# WSN_Atmega8a_V1_2.net
KiCad netlist of a schematic drawn in EAGLE
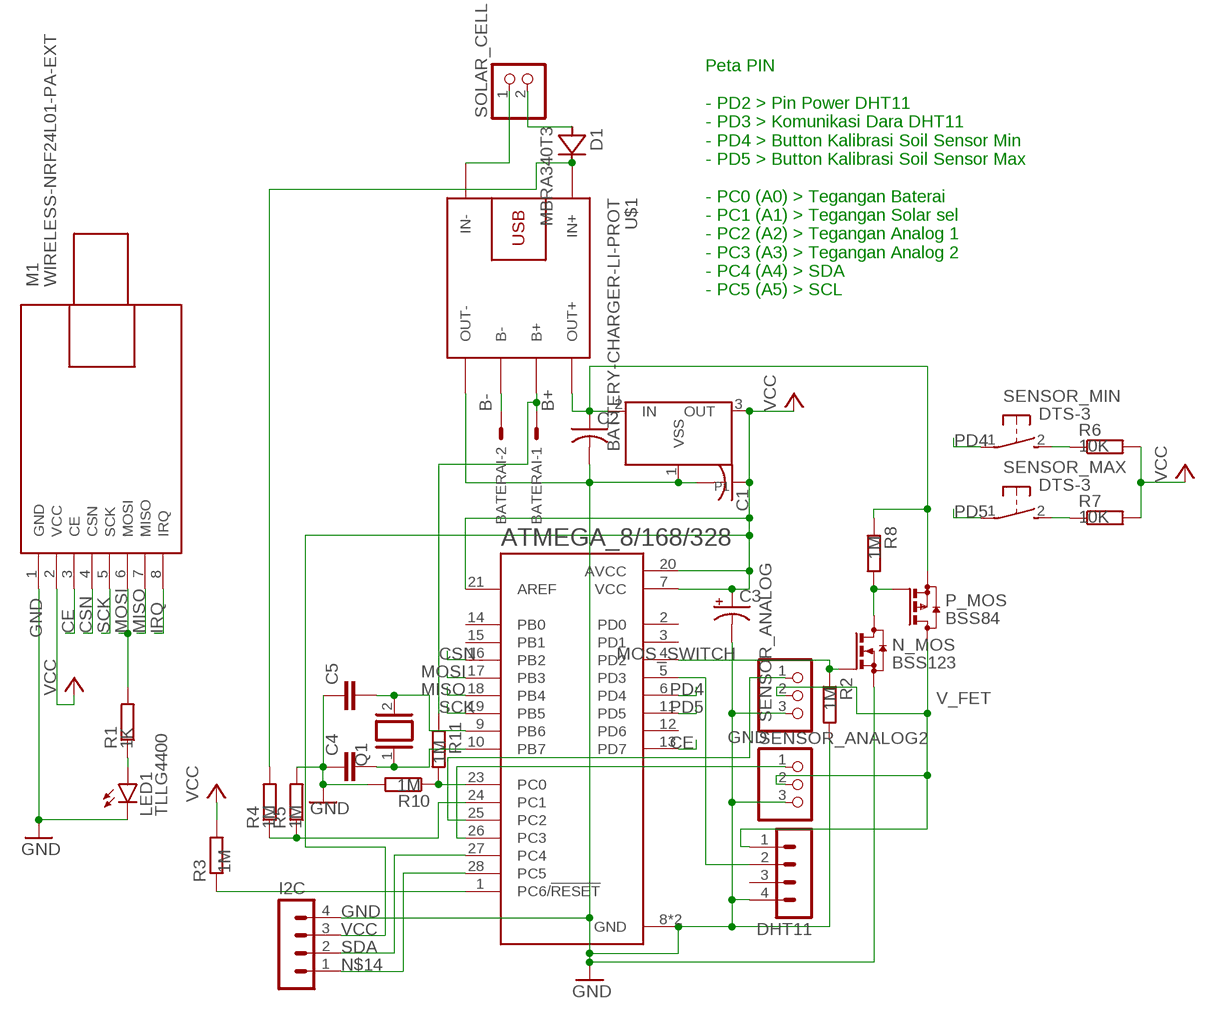
[diagram p0: schematic, sheet 1]

(export (version "E")
  (design (tool "Eeschema 10.0.6"))
  (components
    (comp (ref "ATMEGA_8/168/328")
      (value "ATMEGA328P-PU")
      (footprint "eagle-import:DIP794W46P254L2967H457Q28B")
      (fields (field (name "MF") "Microchip"))
      (libsource (lib "eagle-import") (part "ATMEGA328P-PU"))
    )
    (comp (ref "BATERAI")
      (value "22-23-2021")
      (footprint "eagle-import:22-23-2021")
      (fields (field (name "MF") "MOLEX"))
      (libsource (lib "eagle-import") (part "22-23-2021"))
    )
    (comp (ref "C1")
      (value "C-USC0402")
      (footprint "eagle-import:C0402")
      (libsource (lib "eagle-import") (part "C-USC0402"))
    )
    (comp (ref "C2")
      (value "C-USC0402")
      (footprint "eagle-import:C0402")
      (libsource (lib "eagle-import") (part "C-USC0402"))
    )
    (comp (ref "C3")
      (value "CPOL-USE2.5-6")
      (footprint "eagle-import:E2,5-6")
      (libsource (lib "eagle-import") (part "CPOL-USE2.5-6"))
    )
    (comp (ref "C4")
      (value "C-EU025-024X044")
      (footprint "eagle-import:C025-024X044")
      (libsource (lib "eagle-import") (part "C-EU025-024X044"))
    )
    (comp (ref "C5")
      (value "C-EU025-024X044")
      (footprint "eagle-import:C025-024X044")
      (libsource (lib "eagle-import") (part "C-EU025-024X044"))
    )
    (comp (ref "D1")
      (value "MBRA340T3")
      (footprint "eagle-import:SMA")
      (libsource (lib "eagle-import") (part "MBRA340T3"))
    )
    (comp (ref "DHT11")
      (value "MA04-1")
      (footprint "eagle-import:MA04-1")
      (libsource (lib "eagle-import") (part "MA04-1"))
    )
    (comp (ref "I2C")
      (value "MA04-1")
      (footprint "eagle-import:MA04-1")
      (libsource (lib "eagle-import") (part "MA04-1"))
    )
    (comp (ref "LED1")
      (value "TLLG4400")
      (footprint "eagle-import:LED3MM")
      (fields (field (name "MF") "VISHAY SEMICONDUCTOR"))
      (libsource (lib "eagle-import") (part "TLLG4400"))
    )
    (comp (ref "M1")
      (value "WIRELESS-NRF24L01-PA-EXT")
      (footprint "eagle-import:WIRELESS-NRF24L01-PA-EXT")
      (libsource (lib "eagle-import") (part "WIRELESS-NRF24L01-PA-EXT"))
    )
    (comp (ref "N_MOS")
      (value "BSS123")
      (footprint "eagle-import:SOT23")
      (libsource (lib "eagle-import") (part "BSS123"))
    )
    (comp (ref "P1")
      (value "XC6206SOT-89")
      (footprint "eagle-import:SOT-89")
      (libsource (lib "eagle-import") (part "XC6206SOT-89"))
    )
    (comp (ref "P_MOS")
      (value "BSS84")
      (footprint "eagle-import:SOT23")
      (libsource (lib "eagle-import") (part "BSS84"))
    )
    (comp (ref "Q1")
      (value "XTAL/S")
      (footprint "eagle-import:QS")
      (libsource (lib "eagle-import") (part "XTAL/S"))
    )
    (comp (ref "R1")
      (value "1K")
      (footprint "eagle-import:R0805")
      (libsource (lib "eagle-import") (part "R-EU_R0805"))
    )
    (comp (ref "R2")
      (value "1M")
      (footprint "eagle-import:R0805")
      (libsource (lib "eagle-import") (part "R-EU_R0805"))
    )
    (comp (ref "R3")
      (value "1M")
      (footprint "eagle-import:R0805")
      (libsource (lib "eagle-import") (part "R-EU_R0805"))
    )
    (comp (ref "R4")
      (value "1M")
      (footprint "eagle-import:R0805")
      (libsource (lib "eagle-import") (part "R-EU_R0805"))
    )
    (comp (ref "R5")
      (value "1M")
      (footprint "eagle-import:R0805")
      (libsource (lib "eagle-import") (part "R-EU_R0805"))
    )
    (comp (ref "R6")
      (value "10K")
      (footprint "eagle-import:R0805")
      (libsource (lib "eagle-import") (part "R-EU_R0805"))
    )
    (comp (ref "R7")
      (value "10K")
      (footprint "eagle-import:R0805")
      (libsource (lib "eagle-import") (part "R-EU_R0805"))
    )
    (comp (ref "R8")
      (value "1M")
      (footprint "eagle-import:R0805")
      (libsource (lib "eagle-import") (part "R-EU_R0805"))
    )
    (comp (ref "R10")
      (value "1M")
      (footprint "eagle-import:R0805")
      (libsource (lib "eagle-import") (part "R-EU_R0805"))
    )
    (comp (ref "R11")
      (value "1M")
      (footprint "eagle-import:R0805")
      (libsource (lib "eagle-import") (part "R-EU_R0805"))
    )
    (comp (ref "SENSOR_ANALOG")
      (value "PINHD-1X3/90")
      (footprint "eagle-import:1X03_90")
      (libsource (lib "eagle-import") (part "PINHD-1X3/90"))
    )
    (comp (ref "SENSOR_ANALOG2")
      (value "PINHD-1X3/90")
      (footprint "eagle-import:1X03_90")
      (libsource (lib "eagle-import") (part "PINHD-1X3/90"))
    )
    (comp (ref "SENSOR_MAX")
      (value "DTS-3")
      (footprint "eagle-import:DTS-3")
      (libsource (lib "eagle-import") (part "DTS-3"))
    )
    (comp (ref "SENSOR_MIN")
      (value "DTS-3")
      (footprint "eagle-import:DTS-3")
      (libsource (lib "eagle-import") (part "DTS-3"))
    )
    (comp (ref "SOLAR_CELL")
      (value "PINHD-1X2")
      (footprint "eagle-import:1X02")
      (libsource (lib "eagle-import") (part "PINHD-1X2"))
    )
    (comp (ref "U$1")
      (value "BATTERY-CHARGER-LI-PROT")
      (footprint "eagle-import:BATTERY-CHARGER-LI-PROT")
      (libsource (lib "eagle-import") (part "BATTERY-CHARGER-LI-PROT"))
    )
  )
  (nets
    (net (code "1") (name "/B+") (class "Default")
      (node (ref "BATERAI") (pin "1") (pinfunction "S_1") (pintype "passive"))
      (node (ref "R11") (pin "1") (pinfunction "1_1") (pintype "passive"))
      (node (ref "U$1") (pin "B+") (pinfunction "B+_B+") (pintype "bidirectional"))
    )
    (net (code "2") (name "/B-") (class "Default")
      (node (ref "BATERAI") (pin "2") (pinfunction "S_2") (pintype "passive"))
      (node (ref "U$1") (pin "B-") (pinfunction "B-_B-") (pintype "bidirectional"))
    )
    (net (code "3") (name "/CE") (class "Default")
      (node (ref "ATMEGA_8/168/328") (pin "13") (pinfunction "PD7_13") (pintype "bidirectional"))
      (node (ref "M1") (pin "3") (pinfunction "CE_3") (pintype "bidirectional"))
    )
    (net (code "4") (name "/CSN") (class "Default")
      (node (ref "ATMEGA_8/168/328") (pin "16") (pinfunction "PB2_16") (pintype "bidirectional"))
      (node (ref "M1") (pin "4") (pinfunction "CSN_4") (pintype "bidirectional"))
    )
    (net (code "5") (name "/IRQ") (class "Default")
      (node (ref "M1") (pin "8") (pinfunction "IRQ_8") (pintype "bidirectional"))
    )
    (net (code "6") (name "/MISO") (class "Default")
      (node (ref "ATMEGA_8/168/328") (pin "18") (pinfunction "PB4_18") (pintype "bidirectional"))
      (node (ref "M1") (pin "7") (pinfunction "MISO_7") (pintype "bidirectional"))
    )
    (net (code "7") (name "/MOSI") (class "Default")
      (node (ref "ATMEGA_8/168/328") (pin "17") (pinfunction "PB3_17") (pintype "bidirectional"))
      (node (ref "M1") (pin "6") (pinfunction "MOSI_6") (pintype "bidirectional"))
      (node (ref "R1") (pin "2") (pinfunction "2_2") (pintype "passive"))
    )
    (net (code "8") (name "/MOS_SWITCH") (class "Default")
      (node (ref "ATMEGA_8/168/328") (pin "4") (pinfunction "PD2_4") (pintype "bidirectional"))
      (node (ref "N_MOS") (pin "1") (pinfunction "G_1") (pintype "passive"))
      (node (ref "R2") (pin "1") (pinfunction "1_1") (pintype "passive"))
    )
    (net (code "9") (name "/N$14") (class "Default")
      (node (ref "ATMEGA_8/168/328") (pin "28") (pinfunction "PC5_28") (pintype "bidirectional"))
      (node (ref "I2C") (pin "1") (pinfunction "1_1") (pintype "passive"))
    )
    (net (code "10") (name "/PD4") (class "Default")
      (node (ref "ATMEGA_8/168/328") (pin "6") (pinfunction "PD4_6") (pintype "bidirectional"))
      (node (ref "SENSOR_MIN") (pin "1") (pinfunction "1_1") (pintype "passive"))
    )
    (net (code "11") (name "/PD5") (class "Default")
      (node (ref "ATMEGA_8/168/328") (pin "11") (pinfunction "PD5_11") (pintype "bidirectional"))
      (node (ref "SENSOR_MAX") (pin "1") (pinfunction "1_1") (pintype "passive"))
    )
    (net (code "12") (name "/SCK") (class "Default")
      (node (ref "ATMEGA_8/168/328") (pin "19") (pinfunction "PB5_19") (pintype "bidirectional"))
      (node (ref "M1") (pin "5") (pinfunction "SCK_5") (pintype "bidirectional"))
    )
    (net (code "13") (name "/SDA") (class "Default")
      (node (ref "ATMEGA_8/168/328") (pin "27") (pinfunction "PC4_27") (pintype "bidirectional"))
      (node (ref "I2C") (pin "2") (pinfunction "2_2") (pintype "passive"))
    )
    (net (code "14") (name "/V_FET") (class "Default")
      (node (ref "DHT11") (pin "1") (pinfunction "1_1") (pintype "passive"))
      (node (ref "P_MOS") (pin "3") (pinfunction "D_3") (pintype "passive"))
      (node (ref "SENSOR_ANALOG") (pin "2") (pinfunction "2_2") (pintype "passive"))
      (node (ref "SENSOR_ANALOG2") (pin "2") (pinfunction "2_2") (pintype "passive"))
    )
    (net (code "15") (name "GND") (class "Default")
      (node (ref "ATMEGA_8/168/328") (pin "22") (pinfunction "GND_22") (pintype "power_in"))
      (node (ref "ATMEGA_8/168/328") (pin "8") (pinfunction "GND_8") (pintype "power_in"))
      (node (ref "C1") (pin "2") (pinfunction "2_2") (pintype "passive"))
      (node (ref "C2") (pin "2") (pinfunction "2_2") (pintype "passive"))
      (node (ref "C3") (pin "-") (pinfunction "-_-") (pintype "passive"))
      (node (ref "C4") (pin "1") (pinfunction "1_1") (pintype "passive"))
      (node (ref "C5") (pin "1") (pinfunction "1_1") (pintype "passive"))
      (node (ref "DHT11") (pin "4") (pinfunction "4_4") (pintype "passive"))
      (node (ref "I2C") (pin "4") (pinfunction "4_4") (pintype "passive"))
      (node (ref "LED1") (pin "K") (pinfunction "C_K") (pintype "passive"))
      (node (ref "M1") (pin "1") (pinfunction "GND_1") (pintype "power_in"))
      (node (ref "N_MOS") (pin "2") (pinfunction "S_2") (pintype "passive"))
      (node (ref "P1") (pin "1") (pinfunction "VSS_1") (pintype "bidirectional"))
      (node (ref "R10") (pin "2") (pinfunction "2_2") (pintype "passive"))
      (node (ref "R2") (pin "2") (pinfunction "2_2") (pintype "passive"))
      (node (ref "R5") (pin "2") (pinfunction "2_2") (pintype "passive"))
      (node (ref "SENSOR_ANALOG") (pin "3") (pinfunction "3_3") (pintype "passive"))
      (node (ref "SENSOR_ANALOG2") (pin "3") (pinfunction "3_3") (pintype "passive"))
      (node (ref "U$1") (pin "OUT-") (pinfunction "OUT-_OUT-") (pintype "bidirectional"))
    )
    (net (code "16") (name "Net-(ATMEGA_8/168/328-PB6)") (class "Default")
      (node (ref "ATMEGA_8/168/328") (pin "9") (pinfunction "PB6_9") (pintype "bidirectional"))
      (node (ref "C5") (pin "2") (pinfunction "2_2") (pintype "passive"))
      (node (ref "Q1") (pin "2") (pinfunction "2_2") (pintype "passive"))
    )
    (net (code "17") (name "Net-(ATMEGA_8/168/328-PB7)") (class "Default")
      (node (ref "ATMEGA_8/168/328") (pin "10") (pinfunction "PB7_10") (pintype "bidirectional"))
      (node (ref "C4") (pin "2") (pinfunction "2_2") (pintype "passive"))
      (node (ref "Q1") (pin "1") (pinfunction "1_1") (pintype "passive"))
    )
    (net (code "18") (name "Net-(ATMEGA_8/168/328-PC0)") (class "Default")
      (node (ref "ATMEGA_8/168/328") (pin "23") (pinfunction "PC0_23") (pintype "bidirectional"))
      (node (ref "R10") (pin "1") (pinfunction "1_1") (pintype "passive"))
      (node (ref "R11") (pin "2") (pinfunction "2_2") (pintype "passive"))
    )
    (net (code "19") (name "Net-(ATMEGA_8/168/328-PC1)") (class "Default")
      (node (ref "ATMEGA_8/168/328") (pin "24") (pinfunction "PC1_24") (pintype "bidirectional"))
      (node (ref "R4") (pin "1") (pinfunction "1_1") (pintype "passive"))
      (node (ref "R5") (pin "1") (pinfunction "1_1") (pintype "passive"))
    )
    (net (code "20") (name "Net-(ATMEGA_8/168/328-PC2)") (class "Default")
      (node (ref "ATMEGA_8/168/328") (pin "25") (pinfunction "PC2_25") (pintype "bidirectional"))
      (node (ref "SENSOR_ANALOG") (pin "1") (pinfunction "1_1") (pintype "passive"))
    )
    (net (code "21") (name "Net-(ATMEGA_8/168/328-PC3)") (class "Default")
      (node (ref "ATMEGA_8/168/328") (pin "26") (pinfunction "PC3_26") (pintype "bidirectional"))
      (node (ref "SENSOR_ANALOG2") (pin "1") (pinfunction "1_1") (pintype "passive"))
    )
    (net (code "22") (name "Net-(ATMEGA_8/168/328-PC6{slash}~{RESET})") (class "Default")
      (node (ref "ATMEGA_8/168/328") (pin "1") (pinfunction "PC6/~{RESET}_1") (pintype "bidirectional"))
      (node (ref "R3") (pin "1") (pinfunction "1_1") (pintype "passive"))
    )
    (net (code "23") (name "Net-(ATMEGA_8/168/328-PD3)") (class "Default")
      (node (ref "ATMEGA_8/168/328") (pin "5") (pinfunction "PD3_5") (pintype "bidirectional"))
      (node (ref "DHT11") (pin "2") (pinfunction "2_2") (pintype "passive"))
    )
    (net (code "24") (name "Net-(D1-PadA)") (class "Default")
      (node (ref "D1") (pin "A") (pinfunction "A_A") (pintype "passive"))
      (node (ref "SOLAR_CELL") (pin "2") (pinfunction "2_2") (pintype "passive"))
    )
    (net (code "25") (name "Net-(D1-PadC)") (class "Default")
      (node (ref "D1") (pin "C") (pinfunction "C_C") (pintype "passive"))
      (node (ref "R4") (pin "2") (pinfunction "2_2") (pintype "passive"))
      (node (ref "U$1") (pin "IN+") (pinfunction "IN+_IN+") (pintype "bidirectional"))
    )
    (net (code "26") (name "Net-(LED1-PadA)") (class "Default")
      (node (ref "LED1") (pin "A") (pinfunction "A_A") (pintype "passive"))
      (node (ref "R1") (pin "1") (pinfunction "1_1") (pintype "passive"))
    )
    (net (code "27") (name "Net-(N_MOS-D)") (class "Default")
      (node (ref "N_MOS") (pin "3") (pinfunction "D_3") (pintype "passive"))
      (node (ref "P_MOS") (pin "1") (pinfunction "G_1") (pintype "passive"))
      (node (ref "R8") (pin "2") (pinfunction "2_2") (pintype "passive"))
    )
    (net (code "28") (name "Net-(P1-IN)") (class "Default")
      (node (ref "C2") (pin "1") (pinfunction "1_1") (pintype "passive"))
      (node (ref "P1") (pin "2") (pinfunction "IN_2") (pintype "bidirectional"))
      (node (ref "P_MOS") (pin "2") (pinfunction "S_2") (pintype "passive"))
      (node (ref "R8") (pin "1") (pinfunction "1_1") (pintype "passive"))
      (node (ref "U$1") (pin "OUT+") (pinfunction "OUT+_OUT+") (pintype "bidirectional"))
    )
    (net (code "29") (name "Net-(R6-Pad1)") (class "Default")
      (node (ref "R6") (pin "1") (pinfunction "1_1") (pintype "passive"))
      (node (ref "SENSOR_MIN") (pin "2") (pinfunction "2_2") (pintype "passive"))
    )
    (net (code "30") (name "Net-(R7-Pad1)") (class "Default")
      (node (ref "R7") (pin "1") (pinfunction "1_1") (pintype "passive"))
      (node (ref "SENSOR_MAX") (pin "2") (pinfunction "2_2") (pintype "passive"))
    )
    (net (code "31") (name "Net-(SOLAR_CELL-Pad1)") (class "Default")
      (node (ref "SOLAR_CELL") (pin "1") (pinfunction "1_1") (pintype "passive"))
      (node (ref "U$1") (pin "IN-") (pinfunction "IN-_IN-") (pintype "bidirectional"))
    )
    (net (code "32") (name "VCC") (class "Default")
      (node (ref "ATMEGA_8/168/328") (pin "20") (pinfunction "AVCC_20") (pintype "power_in"))
      (node (ref "ATMEGA_8/168/328") (pin "21") (pinfunction "AREF_21") (pintype "input"))
      (node (ref "ATMEGA_8/168/328") (pin "7") (pinfunction "VCC_7") (pintype "power_in"))
      (node (ref "C1") (pin "1") (pinfunction "1_1") (pintype "passive"))
      (node (ref "C3") (pin "+") (pinfunction "+_+") (pintype "passive"))
      (node (ref "I2C") (pin "3") (pinfunction "3_3") (pintype "passive"))
      (node (ref "M1") (pin "2") (pinfunction "VCC_2") (pintype "power_in"))
      (node (ref "P1") (pin "3") (pinfunction "OUT_3") (pintype "bidirectional"))
      (node (ref "R3") (pin "2") (pinfunction "2_2") (pintype "passive"))
      (node (ref "R6") (pin "2") (pinfunction "2_2") (pintype "passive"))
      (node (ref "R7") (pin "2") (pinfunction "2_2") (pintype "passive"))
    )
    (net (code "33") (name "unconnected-(ATMEGA_8/168/328-PB0-Pad14)") (class "Default")
      (node (ref "ATMEGA_8/168/328") (pin "14") (pinfunction "PB0_14") (pintype "bidirectional"))
    )
    (net (code "34") (name "unconnected-(ATMEGA_8/168/328-PB1-Pad15)") (class "Default")
      (node (ref "ATMEGA_8/168/328") (pin "15") (pinfunction "PB1_15") (pintype "bidirectional"))
    )
    (net (code "35") (name "unconnected-(ATMEGA_8/168/328-PD0-Pad2)") (class "Default")
      (node (ref "ATMEGA_8/168/328") (pin "2") (pinfunction "PD0_2") (pintype "bidirectional"))
    )
    (net (code "36") (name "unconnected-(ATMEGA_8/168/328-PD1-Pad3)") (class "Default")
      (node (ref "ATMEGA_8/168/328") (pin "3") (pinfunction "PD1_3") (pintype "bidirectional"))
    )
    (net (code "37") (name "unconnected-(ATMEGA_8/168/328-PD6-Pad12)") (class "Default")
      (node (ref "ATMEGA_8/168/328") (pin "12") (pinfunction "PD6_12") (pintype "bidirectional"))
    )
    (net (code "38") (name "unconnected-(DHT11-Pad3)") (class "Default")
      (node (ref "DHT11") (pin "3") (pinfunction "3_3") (pintype "passive"))
    )
  )
)
